# project.net
KiCad netlist of a schematic drawn in Altium Designer
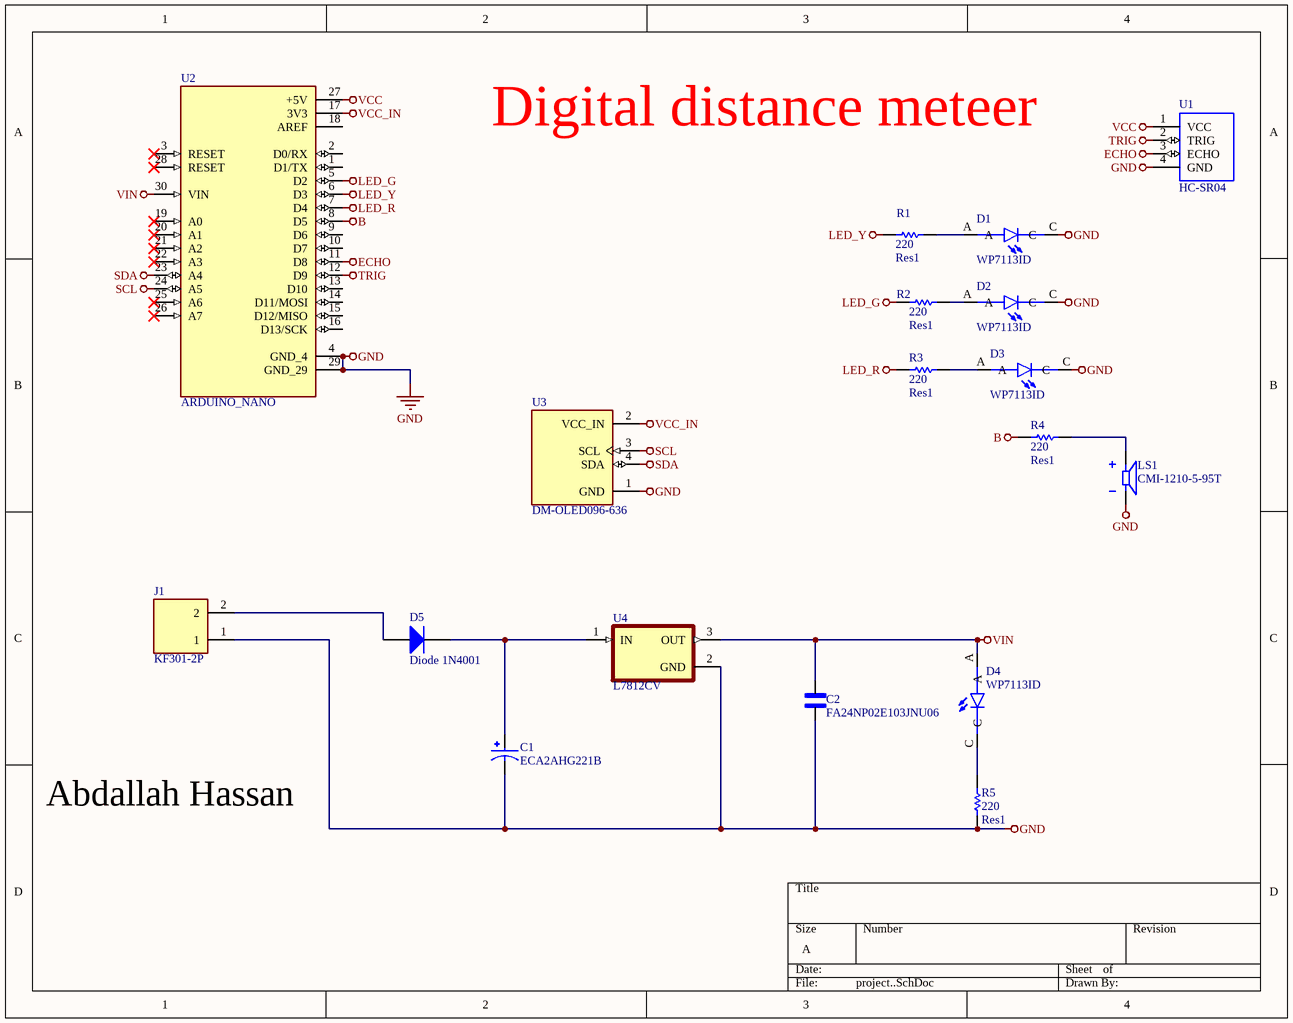
[diagram p0: project..SchDoc]

(export (version "E")
  (design (tool "Eeschema 10.0.6"))
  (components
    (comp (ref "C1")
      (value "ECA2AHG221B")
      (footprint "CAPPRD500W60D1250H2500")
      (description "CAP ALUM 220UF 20% 100V RADIAL")
      (fields (field (name "MF") "Panasonic"))
      (libsource (lib "ECA2AHG221B") (part "ECA2AHG221B"))
    )
    (comp (ref "C2")
      (value "FA24NP02E103JNU06")
      (footprint "CAPRB500W50L450T300H550")
      (description "Cap Ceramic 0.01uF 250V C0G 5% Radial 5mm 150C Automotive Ammo")
      (fields (field (name "MF") "TDK"))
      (libsource (lib "FA24NP02E103JNU06") (part "FA24NP02E103JNU06"))
    )
    (comp (ref "D1")
      (value "WP7113ID")
      (footprint "LED_WP7113ID")
      (description "Red 617nm LED Indication - Discrete 2V Radial")
      (fields (field (name "MF") "Kingbright"))
      (libsource (lib "WP7113ID") (part "WP7113ID"))
    )
    (comp (ref "D2")
      (value "WP7113ID")
      (footprint "LED_WP7113ID")
      (description "Red 617nm LED Indication - Discrete 2V Radial")
      (fields (field (name "MF") "Kingbright"))
      (libsource (lib "WP7113ID") (part "WP7113ID"))
    )
    (comp (ref "D3")
      (value "WP7113ID")
      (footprint "LED_WP7113ID")
      (description "Red 617nm LED Indication - Discrete 2V Radial")
      (fields (field (name "MF") "Kingbright"))
      (libsource (lib "WP7113ID") (part "WP7113ID"))
    )
    (comp (ref "D4")
      (value "WP7113ID")
      (footprint "LED_WP7113ID")
      (description "Red 617nm LED Indication - Discrete 2V Radial")
      (fields (field (name "MF") "Kingbright"))
      (libsource (lib "WP7113ID") (part "WP7113ID"))
    )
    (comp (ref "D5")
      (value "Diode 1N4001")
      (footprint "DO-41")
      (description "1 Amp General Purpose Rectifier")
      (fields (field (name "PUBLISHER") "Altium Limited"))
      (libsource (lib "Miscellaneous Devices") (part "Diode 1N4001"))
    )
    (comp (ref "J1")
      (value "KF301-2P")
      (footprint "HANDSON_KF301-2P")
      (description "2 Pin Terminal Block 5mm Pitch")
      (fields (field (name "MF") "Handson Technology"))
      (libsource (lib "KF301-2P") (part "KF301-2P"))
    )
    (comp (ref "LS1")
      (value "CMI-1210-5-95T")
      (footprint "XDCR_CMI-1210-5-95T")
      (description "12 mm, 5 Vdc, 98 dB, Through Hole, Magnetic Audio Indicator Buzzer")
      (fields (field (name "MF") "Same Sky"))
      (libsource (lib "CMI-1210-5-95T") (part "CMI-1210-5-95T"))
    )
    (comp (ref "R1")
      (value "Res1")
      (footprint "AXIAL-0.3")
      (description "Resistor")
      (fields (field (name "ALTIUM_VALUE") "220") (field (name "PUBLISHER") "Altium Limited"))
      (libsource (lib "Miscellaneous Devices") (part "Res1"))
    )
    (comp (ref "R2")
      (value "Res1")
      (footprint "AXIAL-0.3")
      (description "Resistor")
      (fields (field (name "ALTIUM_VALUE") "220") (field (name "PUBLISHER") "Altium Limited"))
      (libsource (lib "Miscellaneous Devices") (part "Res1"))
    )
    (comp (ref "R3")
      (value "Res1")
      (footprint "AXIAL-0.3")
      (description "Resistor")
      (fields (field (name "ALTIUM_VALUE") "220") (field (name "PUBLISHER") "Altium Limited"))
      (libsource (lib "Miscellaneous Devices") (part "Res1"))
    )
    (comp (ref "R4")
      (value "Res1")
      (footprint "AXIAL-0.3")
      (description "Resistor")
      (fields (field (name "ALTIUM_VALUE") "220") (field (name "PUBLISHER") "Altium Limited"))
      (libsource (lib "Miscellaneous Devices") (part "Res1"))
    )
    (comp (ref "R5")
      (value "Res1")
      (footprint "AXIAL-0.3")
      (description "Resistor")
      (fields (field (name "ALTIUM_VALUE") "220") (field (name "PUBLISHER") "Altium Limited"))
      (libsource (lib "Miscellaneous Devices") (part "Res1"))
    )
    (comp (ref "U1")
      (value "HC-SR04")
      (footprint "XCVR_HC-SR04")
      (description "Ultrasonic Sensor Module")
      (libsource (lib "HC-SR04") (part "HC-SR04"))
    )
    (comp (ref "U2")
      (value "ARDUINO_NANO")
      (footprint "MODULE_ARDUINO_NANO")
      (description "Small, complete, and breadboard-friendly board based on the ATmega328 (Arduino Nano 3.x)")
      (fields (field (name "MF") "Arduino") (field (name "MP") "Arduino Nano"))
      (libsource (lib "ARDUINO_NANO") (part "ARDUINO_NANO"))
    )
    (comp (ref "U3")
      (value "DM-OLED096-636")
      (footprint "MODULE_DM-OLED096-636")
      (description "0.96â€ 128 X 64 MONOCHROME GRAPHIC OLED DISPLAY MODULE - I2C")
      (fields (field (name "MF") "Display Module"))
      (libsource (lib "DM-OLED096-636") (part "DM-OLED096-636"))
    )
    (comp (ref "U4")
      (value "L7812CV")
      (footprint "TO-220-3")
      (description "Linear Voltage Regulator IC Positive Fixed 1 Output 1.5A TO-220")
      (fields (field (name "MF") "STMicroelectronics"))
      (libsource (lib "L7812CV") (part "L7812CV"))
    )
  )
  (nets
    (net (code "1") (name "B") (class "Default")
      (node (ref "R4") (pin "1") (pinfunction "1_1") (pintype "passive"))
      (node (ref "U2") (pin "8") (pinfunction "D5_8") (pintype "bidirectional"))
    )
    (net (code "2") (name "ECHO") (class "Default")
      (node (ref "U1") (pin "3") (pinfunction "ECHO_3") (pintype "bidirectional"))
      (node (ref "U2") (pin "11") (pinfunction "D8_11") (pintype "bidirectional"))
    )
    (net (code "3") (name "GND") (class "Default")
      (node (ref "C1") (pin "N") (pinfunction "N_N") (pintype "passive"))
      (node (ref "C2") (pin "1") (pinfunction "1_1") (pintype "passive"))
      (node (ref "D1") (pin "C") (pinfunction "C_C") (pintype "passive"))
      (node (ref "D2") (pin "C") (pinfunction "C_C") (pintype "passive"))
      (node (ref "D3") (pin "C") (pinfunction "C_C") (pintype "passive"))
      (node (ref "J1") (pin "1") (pinfunction "1_1") (pintype "passive"))
      (node (ref "LS1") (pin "N") (pinfunction "N_N") (pintype "passive"))
      (node (ref "R5") (pin "1") (pinfunction "1_1") (pintype "passive"))
      (node (ref "U1") (pin "4") (pinfunction "GND_4") (pintype "power_in"))
      (node (ref "U2") (pin "29") (pinfunction "GND_29_29") (pintype "power_in"))
      (node (ref "U2") (pin "4") (pinfunction "GND_4_4") (pintype "power_in"))
      (node (ref "U3") (pin "1") (pinfunction "GND_1") (pintype "power_in"))
      (node (ref "U4") (pin "2") (pinfunction "GND_2") (pintype "power_in"))
    )
    (net (code "4") (name "LED_G") (class "Default")
      (node (ref "R2") (pin "1") (pinfunction "1_1") (pintype "passive"))
      (node (ref "U2") (pin "5") (pinfunction "D2_5") (pintype "bidirectional"))
    )
    (net (code "5") (name "LED_R") (class "Default")
      (node (ref "R3") (pin "1") (pinfunction "1_1") (pintype "passive"))
      (node (ref "U2") (pin "7") (pinfunction "D4_7") (pintype "bidirectional"))
    )
    (net (code "6") (name "LED_Y") (class "Default")
      (node (ref "R1") (pin "1") (pinfunction "1_1") (pintype "passive"))
      (node (ref "U2") (pin "6") (pinfunction "D3_6") (pintype "bidirectional"))
    )
    (net (code "7") (name "Net-(D1-PadA)") (class "Default")
      (node (ref "D1") (pin "A") (pinfunction "A_A") (pintype "passive"))
      (node (ref "R1") (pin "2") (pinfunction "2_2") (pintype "passive"))
    )
    (net (code "8") (name "Net-(D2-PadA)") (class "Default")
      (node (ref "D2") (pin "A") (pinfunction "A_A") (pintype "passive"))
      (node (ref "R2") (pin "2") (pinfunction "2_2") (pintype "passive"))
    )
    (net (code "9") (name "Net-(D3-PadA)") (class "Default")
      (node (ref "D3") (pin "A") (pinfunction "A_A") (pintype "passive"))
      (node (ref "R3") (pin "2") (pinfunction "2_2") (pintype "passive"))
    )
    (net (code "10") (name "Net-(D4-PadC)") (class "Default")
      (node (ref "D4") (pin "C") (pinfunction "C_C") (pintype "passive"))
      (node (ref "R5") (pin "2") (pinfunction "2_2") (pintype "passive"))
    )
    (net (code "11") (name "Net-(D5-A)") (class "Default")
      (node (ref "D5") (pin "1") (pinfunction "A_1") (pintype "passive"))
      (node (ref "J1") (pin "2") (pinfunction "2_2") (pintype "passive"))
    )
    (net (code "12") (name "Net-(D5-K)") (class "Default")
      (node (ref "C1") (pin "P") (pinfunction "P_P") (pintype "passive"))
      (node (ref "D5") (pin "2") (pinfunction "K_2") (pintype "passive"))
      (node (ref "U4") (pin "1") (pinfunction "IN_1") (pintype "input"))
    )
    (net (code "13") (name "Net-(LS1-PadP)") (class "Default")
      (node (ref "LS1") (pin "P") (pinfunction "P_P") (pintype "passive"))
      (node (ref "R4") (pin "2") (pinfunction "2_2") (pintype "passive"))
    )
    (net (code "14") (name "SCL") (class "Default")
      (node (ref "U2") (pin "24") (pinfunction "A5_24") (pintype "bidirectional"))
      (node (ref "U3") (pin "3") (pinfunction "SCL_3") (pintype "input"))
    )
    (net (code "15") (name "SDA") (class "Default")
      (node (ref "U2") (pin "23") (pinfunction "A4_23") (pintype "bidirectional"))
      (node (ref "U3") (pin "4") (pinfunction "SDA_4") (pintype "bidirectional"))
    )
    (net (code "16") (name "TRIG") (class "Default")
      (node (ref "U1") (pin "2") (pinfunction "TRIG_2") (pintype "bidirectional"))
      (node (ref "U2") (pin "12") (pinfunction "D9_12") (pintype "bidirectional"))
    )
    (net (code "17") (name "VCC") (class "Default")
      (node (ref "U1") (pin "1") (pinfunction "VCC_1") (pintype "power_in"))
      (node (ref "U2") (pin "27") (pinfunction "+5V_27") (pintype "power_in"))
    )
    (net (code "18") (name "VCC_IN") (class "Default")
      (node (ref "U2") (pin "17") (pinfunction "3V3_17") (pintype "power_in"))
      (node (ref "U3") (pin "2") (pinfunction "VCC_IN_2") (pintype "power_in"))
    )
    (net (code "19") (name "VIN") (class "Default")
      (node (ref "C2") (pin "2") (pinfunction "2_2") (pintype "passive"))
      (node (ref "D4") (pin "A") (pinfunction "A_A") (pintype "passive"))
      (node (ref "U2") (pin "30") (pinfunction "VIN_30") (pintype "input"))
      (node (ref "U4") (pin "3") (pinfunction "OUT_3") (pintype "output"))
    )
    (net (code "20") (name "unconnected-(U2-A0-Pad19)") (class "Default")
      (node (ref "U2") (pin "19") (pinfunction "A0_19") (pintype "input+no_connect"))
    )
    (net (code "21") (name "unconnected-(U2-A1-Pad20)") (class "Default")
      (node (ref "U2") (pin "20") (pinfunction "A1_20") (pintype "input+no_connect"))
    )
    (net (code "22") (name "unconnected-(U2-A2-Pad21)") (class "Default")
      (node (ref "U2") (pin "21") (pinfunction "A2_21") (pintype "input+no_connect"))
    )
    (net (code "23") (name "unconnected-(U2-A3-Pad22)") (class "Default")
      (node (ref "U2") (pin "22") (pinfunction "A3_22") (pintype "input+no_connect"))
    )
    (net (code "24") (name "unconnected-(U2-A6-Pad25)") (class "Default")
      (node (ref "U2") (pin "25") (pinfunction "A6_25") (pintype "input+no_connect"))
    )
    (net (code "25") (name "unconnected-(U2-A7-Pad26)") (class "Default")
      (node (ref "U2") (pin "26") (pinfunction "A7_26") (pintype "input+no_connect"))
    )
    (net (code "26") (name "unconnected-(U2-AREF-Pad18)") (class "Default")
      (node (ref "U2") (pin "18") (pinfunction "AREF_18") (pintype "power_in"))
    )
    (net (code "27") (name "unconnected-(U2-D0{slash}RX-Pad2)") (class "Default")
      (node (ref "U2") (pin "2") (pinfunction "D0/RX_2") (pintype "bidirectional"))
    )
    (net (code "28") (name "unconnected-(U2-D1{slash}TX-Pad1)") (class "Default")
      (node (ref "U2") (pin "1") (pinfunction "D1/TX_1") (pintype "bidirectional"))
    )
    (net (code "29") (name "unconnected-(U2-D6-Pad9)") (class "Default")
      (node (ref "U2") (pin "9") (pinfunction "D6_9") (pintype "bidirectional"))
    )
    (net (code "30") (name "unconnected-(U2-D7-Pad10)") (class "Default")
      (node (ref "U2") (pin "10") (pinfunction "D7_10") (pintype "bidirectional"))
    )
    (net (code "31") (name "unconnected-(U2-D10-Pad13)") (class "Default")
      (node (ref "U2") (pin "13") (pinfunction "D10_13") (pintype "bidirectional"))
    )
    (net (code "32") (name "unconnected-(U2-D11{slash}MOSI-Pad14)") (class "Default")
      (node (ref "U2") (pin "14") (pinfunction "D11/MOSI_14") (pintype "bidirectional"))
    )
    (net (code "33") (name "unconnected-(U2-D12{slash}MISO-Pad15)") (class "Default")
      (node (ref "U2") (pin "15") (pinfunction "D12/MISO_15") (pintype "bidirectional"))
    )
    (net (code "34") (name "unconnected-(U2-D13{slash}SCK-Pad16)") (class "Default")
      (node (ref "U2") (pin "16") (pinfunction "D13/SCK_16") (pintype "bidirectional"))
    )
    (net (code "35") (name "unconnected-(U2-RESET-Pad3)") (class "Default")
      (node (ref "U2") (pin "3") (pinfunction "RESET_3") (pintype "input+no_connect"))
    )
    (net (code "36") (name "unconnected-(U2-RESET-Pad28)") (class "Default")
      (node (ref "U2") (pin "28") (pinfunction "RESET_28") (pintype "input+no_connect"))
    )
  )
)
